# main_rev3.net
KiCad netlist of a schematic drawn in EAGLE
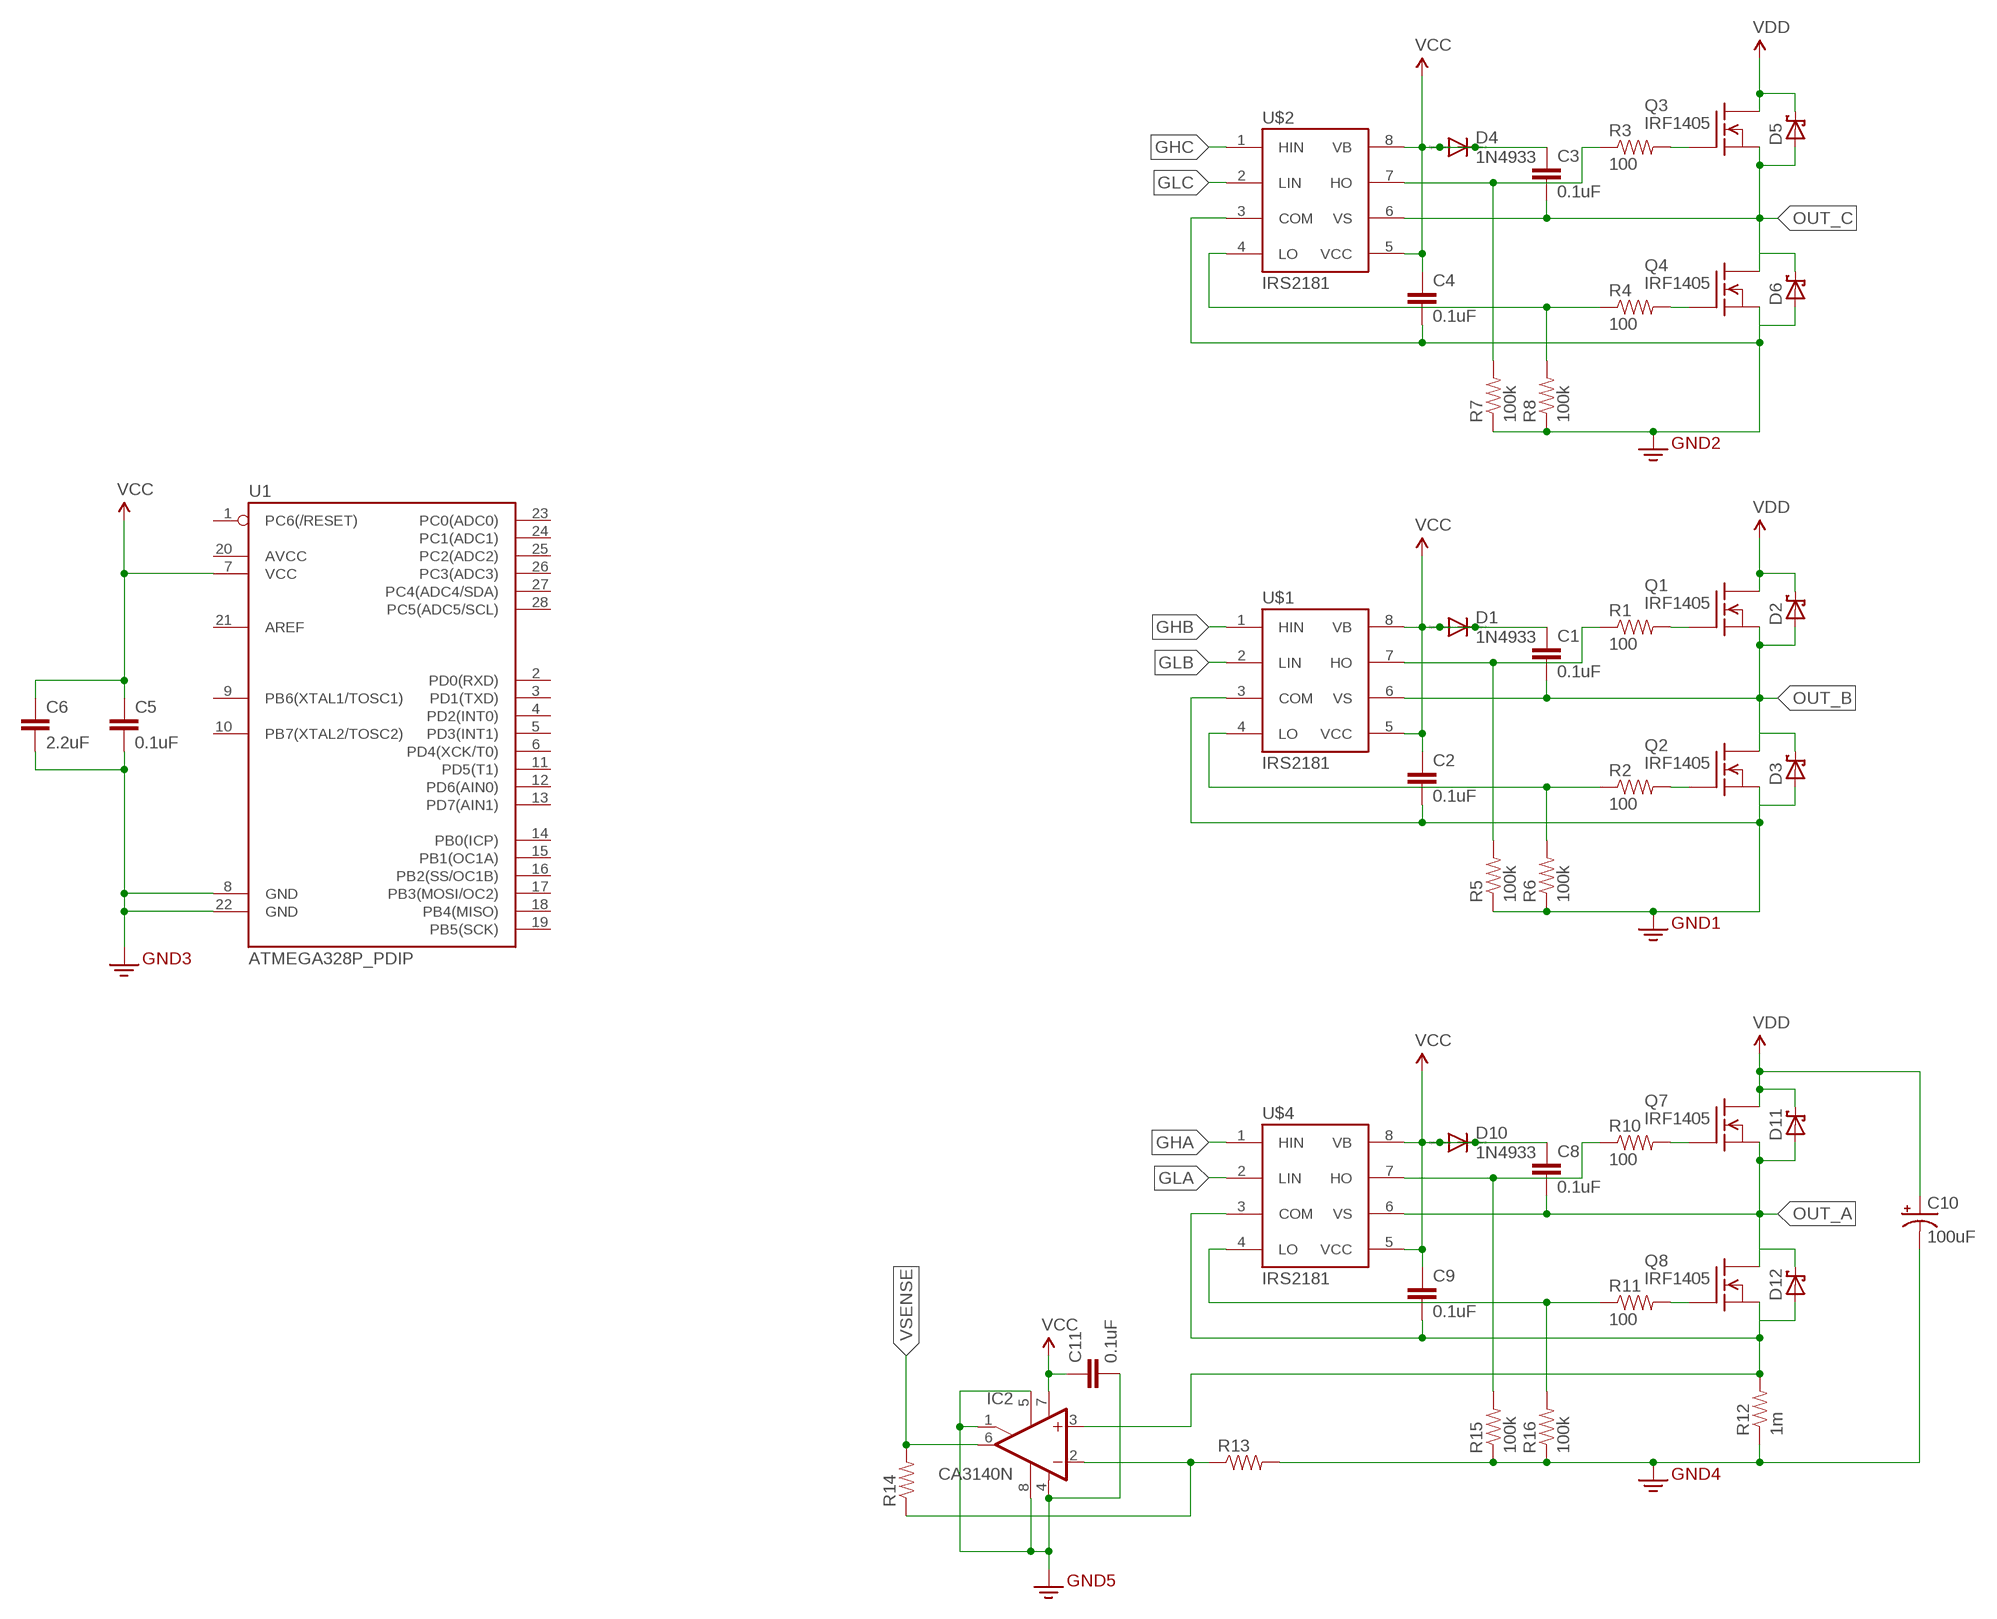
[diagram p0: schematic, sheet 1]

(export (version "E")
  (design (tool "Eeschema 10.0.6"))
  (components
    (comp (ref "C1")
      (value "0.1uF")
      (footprint "eagle-import:0603-CAP")
      (libsource (lib "eagle-import") (part "0.1UF-25V(+80/-20%)(0603)"))
    )
    (comp (ref "C2")
      (value "0.1uF")
      (footprint "eagle-import:0603-CAP")
      (libsource (lib "eagle-import") (part "0.1UF-25V(+80/-20%)(0603)"))
    )
    (comp (ref "C3")
      (value "0.1uF")
      (footprint "eagle-import:0603-CAP")
      (libsource (lib "eagle-import") (part "0.1UF-25V(+80/-20%)(0603)"))
    )
    (comp (ref "C4")
      (value "0.1uF")
      (footprint "eagle-import:0603-CAP")
      (libsource (lib "eagle-import") (part "0.1UF-25V(+80/-20%)(0603)"))
    )
    (comp (ref "C5")
      (value "0.1uF")
      (footprint "eagle-import:0603-CAP")
      (libsource (lib "eagle-import") (part "0.1UF-25V(+80/-20%)(0603)"))
    )
    (comp (ref "C6")
      (value "2.2uF")
      (footprint "eagle-import:0805")
      (libsource (lib "eagle-import") (part "2.2UF-25V-+80/-20(0805)"))
    )
    (comp (ref "C8")
      (value "0.1uF")
      (footprint "eagle-import:0603-CAP")
      (libsource (lib "eagle-import") (part "0.1UF-25V(+80/-20%)(0603)"))
    )
    (comp (ref "C9")
      (value "0.1uF")
      (footprint "eagle-import:0603-CAP")
      (libsource (lib "eagle-import") (part "0.1UF-25V(+80/-20%)(0603)"))
    )
    (comp (ref "C10")
      (value "100uF")
      (footprint "eagle-import:PANASONIC_H13")
      (libsource (lib "eagle-import") (part "100UF-63V-20%(ELECT)"))
    )
    (comp (ref "C11")
      (value "0.1uF")
      (footprint "eagle-import:0603-CAP")
      (libsource (lib "eagle-import") (part "0.1UF-25V(+80/-20%)(0603)"))
    )
    (comp (ref "D1")
      (value "1N4933")
      (footprint "eagle-import:DO41-10")
      (libsource (lib "eagle-import") (part "1N4933"))
    )
    (comp (ref "D2")
      (value "SCHOTTKY-DIODEDO41")
      (footprint "eagle-import:DO41-10")
      (libsource (lib "eagle-import") (part "SCHOTTKY-DIODEDO41"))
    )
    (comp (ref "D3")
      (value "SCHOTTKY-DIODEDO41")
      (footprint "eagle-import:DO41-10")
      (libsource (lib "eagle-import") (part "SCHOTTKY-DIODEDO41"))
    )
    (comp (ref "D4")
      (value "1N4933")
      (footprint "eagle-import:DO41-10")
      (libsource (lib "eagle-import") (part "1N4933"))
    )
    (comp (ref "D5")
      (value "SCHOTTKY-DIODEDO41")
      (footprint "eagle-import:DO41-10")
      (libsource (lib "eagle-import") (part "SCHOTTKY-DIODEDO41"))
    )
    (comp (ref "D6")
      (value "SCHOTTKY-DIODEDO41")
      (footprint "eagle-import:DO41-10")
      (libsource (lib "eagle-import") (part "SCHOTTKY-DIODEDO41"))
    )
    (comp (ref "D10")
      (value "1N4933")
      (footprint "eagle-import:DO41-10")
      (libsource (lib "eagle-import") (part "1N4933"))
    )
    (comp (ref "D11")
      (value "SCHOTTKY-DIODEDO41")
      (footprint "eagle-import:DO41-10")
      (libsource (lib "eagle-import") (part "SCHOTTKY-DIODEDO41"))
    )
    (comp (ref "D12")
      (value "SCHOTTKY-DIODEDO41")
      (footprint "eagle-import:DO41-10")
      (libsource (lib "eagle-import") (part "SCHOTTKY-DIODEDO41"))
    )
    (comp (ref "IC2")
      (value "CA3140N")
      (footprint "eagle-import:DIL08")
      (libsource (lib "eagle-import") (part "CA3140N"))
    )
    (comp (ref "Q1")
      (value "IRF1405")
      (footprint "eagle-import:TO220")
      (libsource (lib "eagle-import") (part "IRF540"))
    )
    (comp (ref "Q2")
      (value "IRF1405")
      (footprint "eagle-import:TO220")
      (libsource (lib "eagle-import") (part "IRF540"))
    )
    (comp (ref "Q3")
      (value "IRF1405")
      (footprint "eagle-import:TO220")
      (libsource (lib "eagle-import") (part "IRF540"))
    )
    (comp (ref "Q4")
      (value "IRF1405")
      (footprint "eagle-import:TO220")
      (libsource (lib "eagle-import") (part "IRF540"))
    )
    (comp (ref "Q7")
      (value "IRF1405")
      (footprint "eagle-import:TO220")
      (libsource (lib "eagle-import") (part "IRF540"))
    )
    (comp (ref "Q8")
      (value "IRF1405")
      (footprint "eagle-import:TO220")
      (libsource (lib "eagle-import") (part "IRF540"))
    )
    (comp (ref "R1")
      (value "100")
      (footprint "eagle-import:AXIAL-0.3")
      (libsource (lib "eagle-import") (part "SparkFun-Resistors_RESISTORAXIAL-0.3"))
    )
    (comp (ref "R2")
      (value "100")
      (footprint "eagle-import:AXIAL-0.3")
      (libsource (lib "eagle-import") (part "SparkFun-Resistors_RESISTORAXIAL-0.3"))
    )
    (comp (ref "R3")
      (value "100")
      (footprint "eagle-import:AXIAL-0.3")
      (libsource (lib "eagle-import") (part "SparkFun-Resistors_RESISTORAXIAL-0.3"))
    )
    (comp (ref "R4")
      (value "100")
      (footprint "eagle-import:AXIAL-0.3")
      (libsource (lib "eagle-import") (part "SparkFun-Resistors_RESISTORAXIAL-0.3"))
    )
    (comp (ref "R5")
      (value "100k")
      (footprint "eagle-import:AXIAL-0.3")
      (libsource (lib "eagle-import") (part "SparkFun-Resistors_RESISTORAXIAL-0.3"))
    )
    (comp (ref "R6")
      (value "100k")
      (footprint "eagle-import:AXIAL-0.3")
      (libsource (lib "eagle-import") (part "SparkFun-Resistors_RESISTORAXIAL-0.3"))
    )
    (comp (ref "R7")
      (value "100k")
      (footprint "eagle-import:AXIAL-0.3")
      (libsource (lib "eagle-import") (part "SparkFun-Resistors_RESISTORAXIAL-0.3"))
    )
    (comp (ref "R8")
      (value "100k")
      (footprint "eagle-import:AXIAL-0.3")
      (libsource (lib "eagle-import") (part "SparkFun-Resistors_RESISTORAXIAL-0.3"))
    )
    (comp (ref "R10")
      (value "100")
      (footprint "eagle-import:AXIAL-0.3")
      (libsource (lib "eagle-import") (part "SparkFun-Resistors_RESISTORAXIAL-0.3"))
    )
    (comp (ref "R11")
      (value "100")
      (footprint "eagle-import:AXIAL-0.3")
      (libsource (lib "eagle-import") (part "SparkFun-Resistors_RESISTORAXIAL-0.3"))
    )
    (comp (ref "R12")
      (value "1m")
      (footprint "eagle-import:AXIAL-0.8")
      (libsource (lib "eagle-import") (part "RESISTORPTH-2W"))
    )
    (comp (ref "R13")
      (value "RESISTORAXIAL-0.3")
      (footprint "eagle-import:AXIAL-0.3")
      (libsource (lib "eagle-import") (part "SparkFun-Resistors_RESISTORAXIAL-0.3"))
    )
    (comp (ref "R14")
      (value "RESISTORAXIAL-0.3")
      (footprint "eagle-import:AXIAL-0.3")
      (libsource (lib "eagle-import") (part "SparkFun-Resistors_RESISTORAXIAL-0.3"))
    )
    (comp (ref "R15")
      (value "100k")
      (footprint "eagle-import:AXIAL-0.3")
      (libsource (lib "eagle-import") (part "SparkFun-Resistors_RESISTORAXIAL-0.3"))
    )
    (comp (ref "R16")
      (value "100k")
      (footprint "eagle-import:AXIAL-0.3")
      (libsource (lib "eagle-import") (part "SparkFun-Resistors_RESISTORAXIAL-0.3"))
    )
    (comp (ref "U$1")
      (value "IRS2181")
      (footprint "eagle-import:DIP08")
      (libsource (lib "eagle-import") (part "IRS2181"))
    )
    (comp (ref "U$2")
      (value "IRS2181")
      (footprint "eagle-import:DIP08")
      (libsource (lib "eagle-import") (part "IRS2181"))
    )
    (comp (ref "U$4")
      (value "IRS2181")
      (footprint "eagle-import:DIP08")
      (libsource (lib "eagle-import") (part "IRS2181"))
    )
    (comp (ref "U1")
      (value "ATMEGA328P_PDIP")
      (footprint "eagle-import:DIL28-3")
      (libsource (lib "eagle-import") (part "ATMEGA328P_PDIP"))
    )
  )
  (nets
    (net (code "1") (name "GHA") (class "Default")
      (node (ref "U$4") (pin "1") (pinfunction "HIN_1") (pintype "bidirectional"))
    )
    (net (code "2") (name "GHB") (class "Default")
      (node (ref "U$1") (pin "1") (pinfunction "HIN_1") (pintype "bidirectional"))
    )
    (net (code "3") (name "GHC") (class "Default")
      (node (ref "U$2") (pin "1") (pinfunction "HIN_1") (pintype "bidirectional"))
    )
    (net (code "4") (name "GLA") (class "Default")
      (node (ref "U$4") (pin "2") (pinfunction "LIN_2") (pintype "bidirectional"))
    )
    (net (code "5") (name "GLB") (class "Default")
      (node (ref "U$1") (pin "2") (pinfunction "LIN_2") (pintype "bidirectional"))
    )
    (net (code "6") (name "GLC") (class "Default")
      (node (ref "U$2") (pin "2") (pinfunction "LIN_2") (pintype "bidirectional"))
    )
    (net (code "7") (name "GND2") (class "Default")
      (node (ref "C10") (pin "-") (pinfunction "-_-") (pintype "passive"))
      (node (ref "C11") (pin "2") (pinfunction "2_2") (pintype "passive"))
      (node (ref "C2") (pin "2") (pinfunction "2_2") (pintype "passive"))
      (node (ref "C4") (pin "2") (pinfunction "2_2") (pintype "passive"))
      (node (ref "C5") (pin "2") (pinfunction "2_2") (pintype "passive"))
      (node (ref "C6") (pin "2") (pinfunction "2_2") (pintype "passive"))
      (node (ref "IC2") (pin "1") (pinfunction "ON/CMP_1") (pintype "passive"))
      (node (ref "IC2") (pin "4") (pinfunction "V-_4") (pintype "power_in"))
      (node (ref "IC2") (pin "5") (pinfunction "ON_5") (pintype "passive"))
      (node (ref "IC2") (pin "8") (pinfunction "CMP_8") (pintype "passive"))
      (node (ref "Q2") (pin "3") (pinfunction "S_3") (pintype "passive"))
      (node (ref "Q4") (pin "3") (pinfunction "S_3") (pintype "passive"))
      (node (ref "R12") (pin "P$1") (pinfunction "1_P$1") (pintype "passive"))
      (node (ref "R13") (pin "P$2") (pinfunction "2_P$2") (pintype "passive"))
      (node (ref "R15") (pin "P$1") (pinfunction "1_P$1") (pintype "passive"))
      (node (ref "R16") (pin "P$1") (pinfunction "1_P$1") (pintype "passive"))
      (node (ref "R5") (pin "P$1") (pinfunction "1_P$1") (pintype "passive"))
      (node (ref "R6") (pin "P$1") (pinfunction "1_P$1") (pintype "passive"))
      (node (ref "R7") (pin "P$1") (pinfunction "1_P$1") (pintype "passive"))
      (node (ref "R8") (pin "P$1") (pinfunction "1_P$1") (pintype "passive"))
      (node (ref "U$1") (pin "3") (pinfunction "COM_3") (pintype "bidirectional"))
      (node (ref "U$2") (pin "3") (pinfunction "COM_3") (pintype "bidirectional"))
      (node (ref "U1") (pin "22") (pinfunction "GND_22") (pintype "bidirectional"))
      (node (ref "U1") (pin "8") (pinfunction "GND_8") (pintype "bidirectional"))
    )
    (net (code "8") (name "Net-(IC2-+IN)") (class "Default")
      (node (ref "C9") (pin "2") (pinfunction "2_2") (pintype "passive"))
      (node (ref "IC2") (pin "3") (pinfunction "+IN_3") (pintype "input"))
      (node (ref "Q8") (pin "3") (pinfunction "S_3") (pintype "passive"))
      (node (ref "R12") (pin "P$2") (pinfunction "2_P$2") (pintype "passive"))
      (node (ref "U$4") (pin "3") (pinfunction "COM_3") (pintype "bidirectional"))
    )
    (net (code "9") (name "Net-(IC2--IN)") (class "Default")
      (node (ref "IC2") (pin "2") (pinfunction "-IN_2") (pintype "input"))
      (node (ref "R13") (pin "P$1") (pinfunction "1_P$1") (pintype "passive"))
      (node (ref "R14") (pin "P$1") (pinfunction "1_P$1") (pintype "passive"))
    )
    (net (code "10") (name "Net-(Q1-G)") (class "Default")
      (node (ref "Q1") (pin "1") (pinfunction "G_1") (pintype "passive"))
      (node (ref "R1") (pin "P$2") (pinfunction "2_P$2") (pintype "passive"))
    )
    (net (code "11") (name "Net-(Q2-G)") (class "Default")
      (node (ref "Q2") (pin "1") (pinfunction "G_1") (pintype "passive"))
      (node (ref "R2") (pin "P$2") (pinfunction "2_P$2") (pintype "passive"))
    )
    (net (code "12") (name "Net-(Q3-G)") (class "Default")
      (node (ref "Q3") (pin "1") (pinfunction "G_1") (pintype "passive"))
      (node (ref "R3") (pin "P$2") (pinfunction "2_P$2") (pintype "passive"))
    )
    (net (code "13") (name "Net-(Q4-G)") (class "Default")
      (node (ref "Q4") (pin "1") (pinfunction "G_1") (pintype "passive"))
      (node (ref "R4") (pin "P$2") (pinfunction "2_P$2") (pintype "passive"))
    )
    (net (code "14") (name "Net-(Q7-G)") (class "Default")
      (node (ref "Q7") (pin "1") (pinfunction "G_1") (pintype "passive"))
      (node (ref "R10") (pin "P$2") (pinfunction "2_P$2") (pintype "passive"))
    )
    (net (code "15") (name "Net-(Q8-G)") (class "Default")
      (node (ref "Q8") (pin "1") (pinfunction "G_1") (pintype "passive"))
      (node (ref "R11") (pin "P$2") (pinfunction "2_P$2") (pintype "passive"))
    )
    (net (code "16") (name "Net-(R1-1)") (class "Default")
      (node (ref "R1") (pin "P$1") (pinfunction "1_P$1") (pintype "passive"))
      (node (ref "R5") (pin "P$2") (pinfunction "2_P$2") (pintype "passive"))
      (node (ref "U$1") (pin "7") (pinfunction "HO_7") (pintype "bidirectional"))
    )
    (net (code "17") (name "Net-(R2-1)") (class "Default")
      (node (ref "R2") (pin "P$1") (pinfunction "1_P$1") (pintype "passive"))
      (node (ref "R6") (pin "P$2") (pinfunction "2_P$2") (pintype "passive"))
      (node (ref "U$1") (pin "4") (pinfunction "LO_4") (pintype "bidirectional"))
    )
    (net (code "18") (name "Net-(R3-1)") (class "Default")
      (node (ref "R3") (pin "P$1") (pinfunction "1_P$1") (pintype "passive"))
      (node (ref "R7") (pin "P$2") (pinfunction "2_P$2") (pintype "passive"))
      (node (ref "U$2") (pin "7") (pinfunction "HO_7") (pintype "bidirectional"))
    )
    (net (code "19") (name "Net-(R4-1)") (class "Default")
      (node (ref "R4") (pin "P$1") (pinfunction "1_P$1") (pintype "passive"))
      (node (ref "R8") (pin "P$2") (pinfunction "2_P$2") (pintype "passive"))
      (node (ref "U$2") (pin "4") (pinfunction "LO_4") (pintype "bidirectional"))
    )
    (net (code "20") (name "Net-(R10-1)") (class "Default")
      (node (ref "R10") (pin "P$1") (pinfunction "1_P$1") (pintype "passive"))
      (node (ref "R15") (pin "P$2") (pinfunction "2_P$2") (pintype "passive"))
      (node (ref "U$4") (pin "7") (pinfunction "HO_7") (pintype "bidirectional"))
    )
    (net (code "21") (name "Net-(R11-1)") (class "Default")
      (node (ref "R11") (pin "P$1") (pinfunction "1_P$1") (pintype "passive"))
      (node (ref "R16") (pin "P$2") (pinfunction "2_P$2") (pintype "passive"))
      (node (ref "U$4") (pin "4") (pinfunction "LO_4") (pintype "bidirectional"))
    )
    (net (code "22") (name "OUT_A") (class "Default")
      (node (ref "C8") (pin "2") (pinfunction "2_2") (pintype "passive"))
      (node (ref "D11") (pin "A") (pinfunction "A_A") (pintype "passive"))
      (node (ref "Q7") (pin "3") (pinfunction "S_3") (pintype "passive"))
      (node (ref "Q8") (pin "2") (pinfunction "D_2") (pintype "passive"))
      (node (ref "U$4") (pin "6") (pinfunction "VS_6") (pintype "bidirectional"))
    )
    (net (code "23") (name "OUT_B") (class "Default")
      (node (ref "C1") (pin "2") (pinfunction "2_2") (pintype "passive"))
      (node (ref "D2") (pin "A") (pinfunction "A_A") (pintype "passive"))
      (node (ref "Q1") (pin "3") (pinfunction "S_3") (pintype "passive"))
      (node (ref "Q2") (pin "2") (pinfunction "D_2") (pintype "passive"))
      (node (ref "U$1") (pin "6") (pinfunction "VS_6") (pintype "bidirectional"))
    )
    (net (code "24") (name "OUT_C") (class "Default")
      (node (ref "C3") (pin "2") (pinfunction "2_2") (pintype "passive"))
      (node (ref "D5") (pin "A") (pinfunction "A_A") (pintype "passive"))
      (node (ref "Q3") (pin "3") (pinfunction "S_3") (pintype "passive"))
      (node (ref "Q4") (pin "2") (pinfunction "D_2") (pintype "passive"))
      (node (ref "U$2") (pin "6") (pinfunction "VS_6") (pintype "bidirectional"))
    )
    (net (code "25") (name "VCC") (class "Default")
      (node (ref "C1") (pin "1") (pinfunction "1_1") (pintype "passive"))
      (node (ref "C11") (pin "1") (pinfunction "1_1") (pintype "passive"))
      (node (ref "C2") (pin "1") (pinfunction "1_1") (pintype "passive"))
      (node (ref "C3") (pin "1") (pinfunction "1_1") (pintype "passive"))
      (node (ref "C4") (pin "1") (pinfunction "1_1") (pintype "passive"))
      (node (ref "C5") (pin "1") (pinfunction "1_1") (pintype "passive"))
      (node (ref "C6") (pin "1") (pinfunction "1_1") (pintype "passive"))
      (node (ref "C8") (pin "1") (pinfunction "1_1") (pintype "passive"))
      (node (ref "C9") (pin "1") (pinfunction "1_1") (pintype "passive"))
      (node (ref "D1") (pin "A") (pinfunction "A_A") (pintype "passive"))
      (node (ref "D1") (pin "C") (pinfunction "C_C") (pintype "passive"))
      (node (ref "D10") (pin "A") (pinfunction "A_A") (pintype "passive"))
      (node (ref "D10") (pin "C") (pinfunction "C_C") (pintype "passive"))
      (node (ref "D4") (pin "A") (pinfunction "A_A") (pintype "passive"))
      (node (ref "D4") (pin "C") (pinfunction "C_C") (pintype "passive"))
      (node (ref "IC2") (pin "7") (pinfunction "V+_7") (pintype "power_in"))
      (node (ref "U$1") (pin "5") (pinfunction "VCC_5") (pintype "bidirectional"))
      (node (ref "U$1") (pin "8") (pinfunction "VB_8") (pintype "bidirectional"))
      (node (ref "U$2") (pin "5") (pinfunction "VCC_5") (pintype "bidirectional"))
      (node (ref "U$2") (pin "8") (pinfunction "VB_8") (pintype "bidirectional"))
      (node (ref "U$4") (pin "5") (pinfunction "VCC_5") (pintype "bidirectional"))
      (node (ref "U$4") (pin "8") (pinfunction "VB_8") (pintype "bidirectional"))
      (node (ref "U1") (pin "7") (pinfunction "VCC_7") (pintype "bidirectional"))
    )
    (net (code "26") (name "VDD") (class "Default")
      (node (ref "C10") (pin "+") (pinfunction "+_+") (pintype "passive"))
      (node (ref "D11") (pin "C") (pinfunction "C_C") (pintype "passive"))
      (node (ref "D2") (pin "C") (pinfunction "C_C") (pintype "passive"))
      (node (ref "D5") (pin "C") (pinfunction "C_C") (pintype "passive"))
      (node (ref "Q1") (pin "2") (pinfunction "D_2") (pintype "passive"))
      (node (ref "Q3") (pin "2") (pinfunction "D_2") (pintype "passive"))
      (node (ref "Q7") (pin "2") (pinfunction "D_2") (pintype "passive"))
    )
    (net (code "27") (name "VSENSE") (class "Default")
      (node (ref "IC2") (pin "6") (pinfunction "OUT_6") (pintype "output"))
      (node (ref "R14") (pin "P$2") (pinfunction "2_P$2") (pintype "passive"))
    )
    (net (code "28") (name "unconnected-(D3-PadA)") (class "Default")
      (node (ref "D3") (pin "A") (pinfunction "A_A") (pintype "passive"))
    )
    (net (code "29") (name "unconnected-(D3-PadC)") (class "Default")
      (node (ref "D3") (pin "C") (pinfunction "C_C") (pintype "passive"))
    )
    (net (code "30") (name "unconnected-(D6-PadA)") (class "Default")
      (node (ref "D6") (pin "A") (pinfunction "A_A") (pintype "passive"))
    )
    (net (code "31") (name "unconnected-(D6-PadC)") (class "Default")
      (node (ref "D6") (pin "C") (pinfunction "C_C") (pintype "passive"))
    )
    (net (code "32") (name "unconnected-(D12-PadA)") (class "Default")
      (node (ref "D12") (pin "A") (pinfunction "A_A") (pintype "passive"))
    )
    (net (code "33") (name "unconnected-(D12-PadC)") (class "Default")
      (node (ref "D12") (pin "C") (pinfunction "C_C") (pintype "passive"))
    )
    (net (code "34") (name "unconnected-(U1-AREF-Pad21)") (class "Default")
      (node (ref "U1") (pin "21") (pinfunction "AREF_21") (pintype "bidirectional"))
    )
    (net (code "35") (name "unconnected-(U1-AVCC-Pad20)") (class "Default")
      (node (ref "U1") (pin "20") (pinfunction "AVCC_20") (pintype "bidirectional"))
    )
    (net (code "36") (name "unconnected-(U1-PB0(ICP)-Pad14)") (class "Default")
      (node (ref "U1") (pin "14") (pinfunction "PB0(ICP)_14") (pintype "bidirectional"))
    )
    (net (code "37") (name "unconnected-(U1-PB1(OC1A)-Pad15)") (class "Default")
      (node (ref "U1") (pin "15") (pinfunction "PB1(OC1A)_15") (pintype "bidirectional"))
    )
    (net (code "38") (name "unconnected-(U1-PB2(SS{slash}OC1B)-Pad16)") (class "Default")
      (node (ref "U1") (pin "16") (pinfunction "PB2(SS/OC1B)_16") (pintype "bidirectional"))
    )
    (net (code "39") (name "unconnected-(U1-PB3(MOSI{slash}OC2)-Pad17)") (class "Default")
      (node (ref "U1") (pin "17") (pinfunction "PB3(MOSI/OC2)_17") (pintype "bidirectional"))
    )
    (net (code "40") (name "unconnected-(U1-PB4(MISO)-Pad18)") (class "Default")
      (node (ref "U1") (pin "18") (pinfunction "PB4(MISO)_18") (pintype "bidirectional"))
    )
    (net (code "41") (name "unconnected-(U1-PB5(SCK)-Pad19)") (class "Default")
      (node (ref "U1") (pin "19") (pinfunction "PB5(SCK)_19") (pintype "bidirectional"))
    )
    (net (code "42") (name "unconnected-(U1-PB6(XTAL1{slash}TOSC1)-Pad9)") (class "Default")
      (node (ref "U1") (pin "9") (pinfunction "PB6(XTAL1/TOSC1)_9") (pintype "bidirectional"))
    )
    (net (code "43") (name "unconnected-(U1-PB7(XTAL2{slash}TOSC2)-Pad10)") (class "Default")
      (node (ref "U1") (pin "10") (pinfunction "PB7(XTAL2/TOSC2)_10") (pintype "bidirectional"))
    )
    (net (code "44") (name "unconnected-(U1-PC0(ADC0)-Pad23)") (class "Default")
      (node (ref "U1") (pin "23") (pinfunction "PC0(ADC0)_23") (pintype "bidirectional"))
    )
    (net (code "45") (name "unconnected-(U1-PC1(ADC1)-Pad24)") (class "Default")
      (node (ref "U1") (pin "24") (pinfunction "PC1(ADC1)_24") (pintype "bidirectional"))
    )
    (net (code "46") (name "unconnected-(U1-PC2(ADC2)-Pad25)") (class "Default")
      (node (ref "U1") (pin "25") (pinfunction "PC2(ADC2)_25") (pintype "bidirectional"))
    )
    (net (code "47") (name "unconnected-(U1-PC3(ADC3)-Pad26)") (class "Default")
      (node (ref "U1") (pin "26") (pinfunction "PC3(ADC3)_26") (pintype "bidirectional"))
    )
    (net (code "48") (name "unconnected-(U1-PC4(ADC4{slash}SDA)-Pad27)") (class "Default")
      (node (ref "U1") (pin "27") (pinfunction "PC4(ADC4/SDA)_27") (pintype "bidirectional"))
    )
    (net (code "49") (name "unconnected-(U1-PC5(ADC5{slash}SCL)-Pad28)") (class "Default")
      (node (ref "U1") (pin "28") (pinfunction "PC5(ADC5/SCL)_28") (pintype "bidirectional"))
    )
    (net (code "50") (name "unconnected-(U1-PC6({slash}RESET)-Pad1)") (class "Default")
      (node (ref "U1") (pin "1") (pinfunction "PC6(/RESET)_1") (pintype "bidirectional"))
    )
    (net (code "51") (name "unconnected-(U1-PD0(RXD)-Pad2)") (class "Default")
      (node (ref "U1") (pin "2") (pinfunction "PD0(RXD)_2") (pintype "bidirectional"))
    )
    (net (code "52") (name "unconnected-(U1-PD1(TXD)-Pad3)") (class "Default")
      (node (ref "U1") (pin "3") (pinfunction "PD1(TXD)_3") (pintype "bidirectional"))
    )
    (net (code "53") (name "unconnected-(U1-PD2(INT0)-Pad4)") (class "Default")
      (node (ref "U1") (pin "4") (pinfunction "PD2(INT0)_4") (pintype "bidirectional"))
    )
    (net (code "54") (name "unconnected-(U1-PD3(INT1)-Pad5)") (class "Default")
      (node (ref "U1") (pin "5") (pinfunction "PD3(INT1)_5") (pintype "bidirectional"))
    )
    (net (code "55") (name "unconnected-(U1-PD4(XCK{slash}T0)-Pad6)") (class "Default")
      (node (ref "U1") (pin "6") (pinfunction "PD4(XCK/T0)_6") (pintype "bidirectional"))
    )
    (net (code "56") (name "unconnected-(U1-PD5(T1)-Pad11)") (class "Default")
      (node (ref "U1") (pin "11") (pinfunction "PD5(T1)_11") (pintype "bidirectional"))
    )
    (net (code "57") (name "unconnected-(U1-PD6(AIN0)-Pad12)") (class "Default")
      (node (ref "U1") (pin "12") (pinfunction "PD6(AIN0)_12") (pintype "bidirectional"))
    )
    (net (code "58") (name "unconnected-(U1-PD7(AIN1)-Pad13)") (class "Default")
      (node (ref "U1") (pin "13") (pinfunction "PD7(AIN1)_13") (pintype "bidirectional"))
    )
  )
)
